# cm4_adc.net
KiCad netlist of a schematic drawn in EAGLE
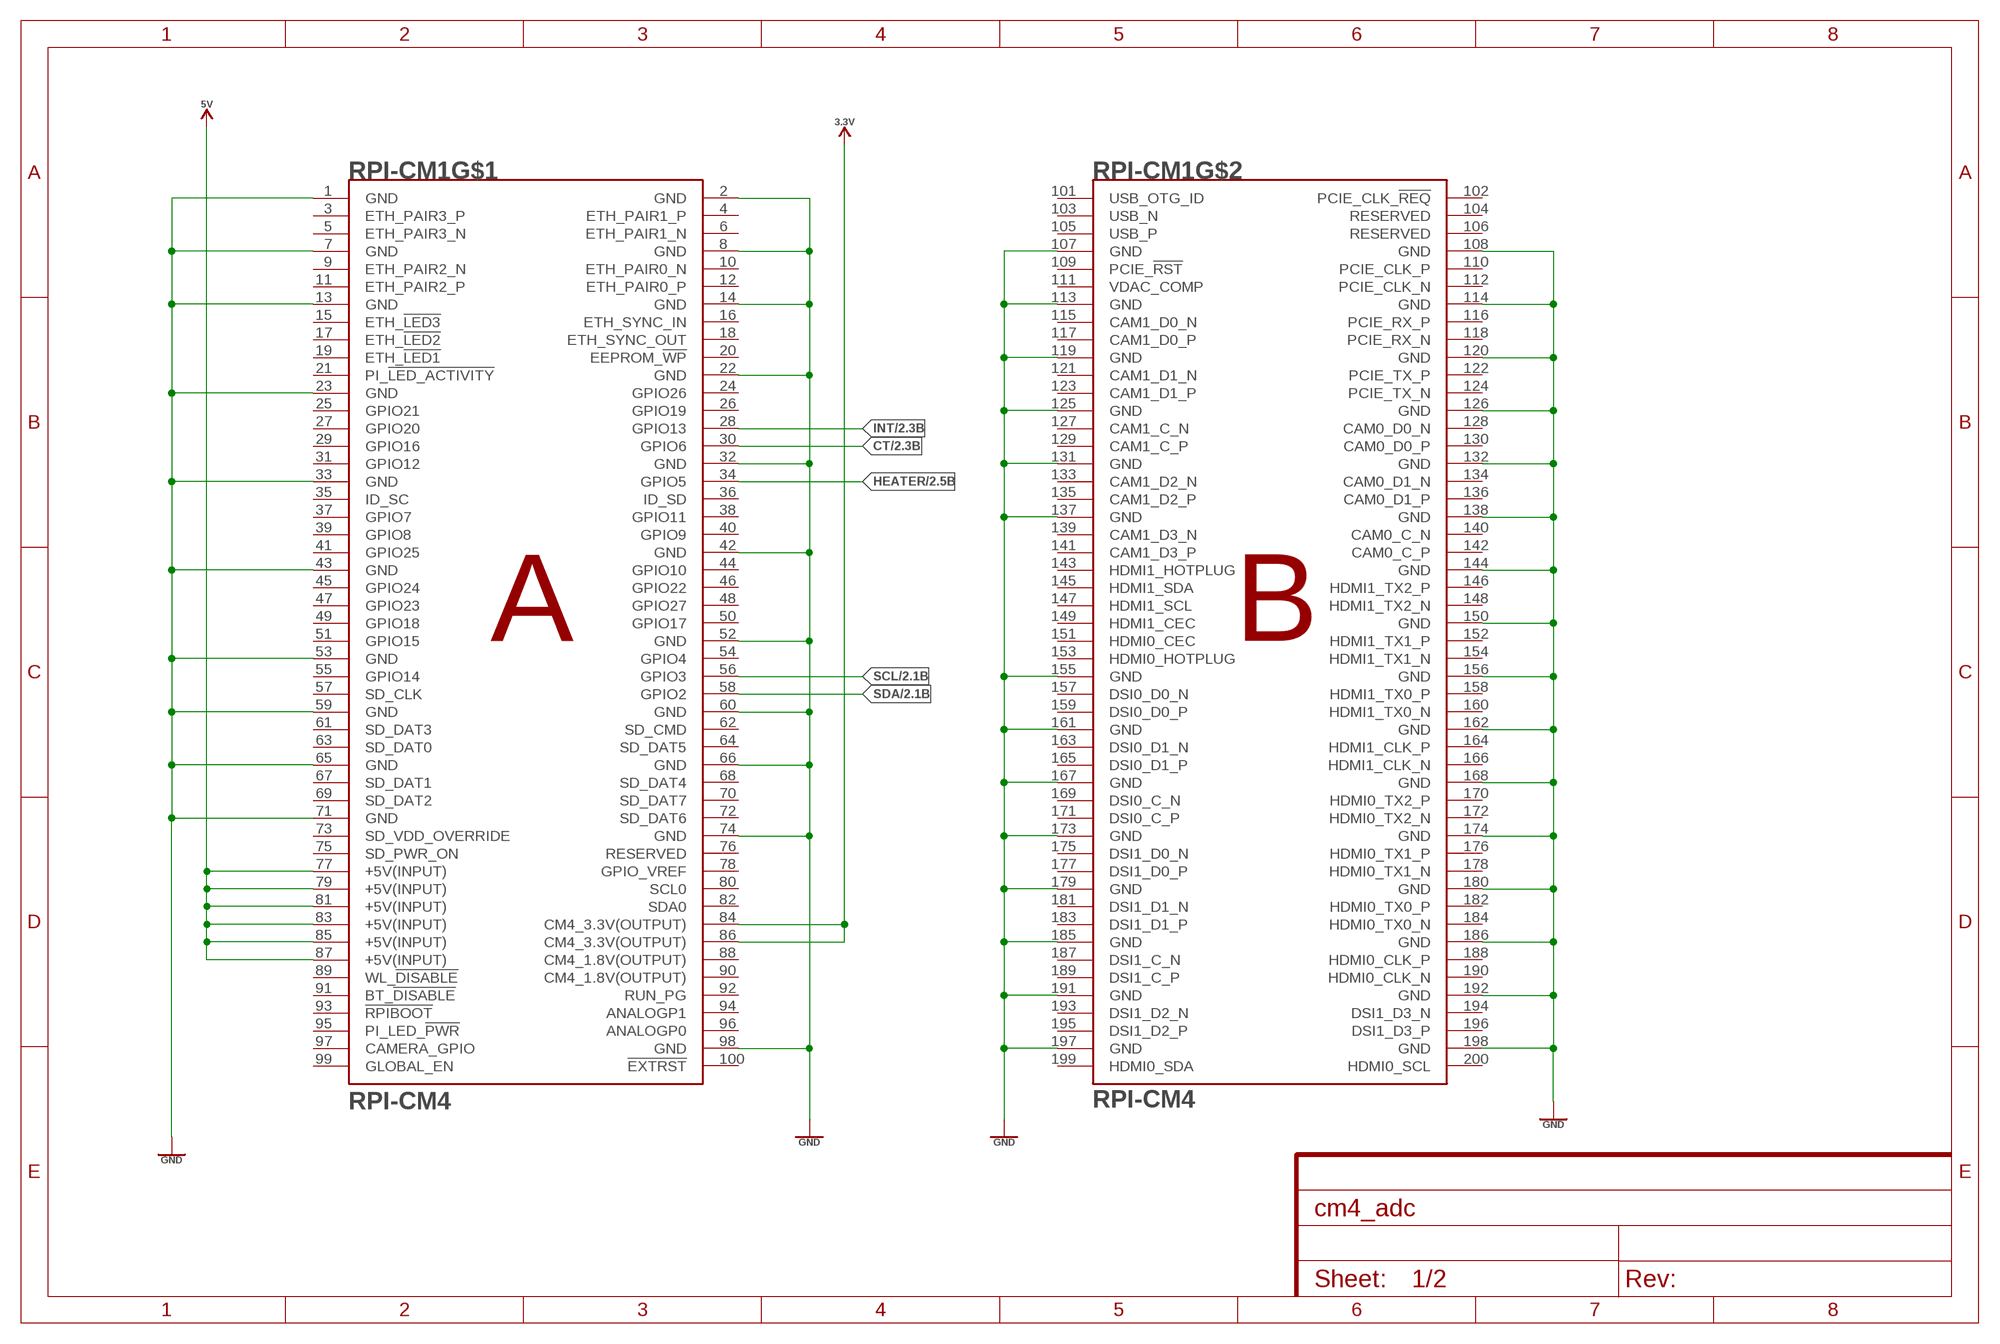
[diagram p0: schematic, sheet 1]
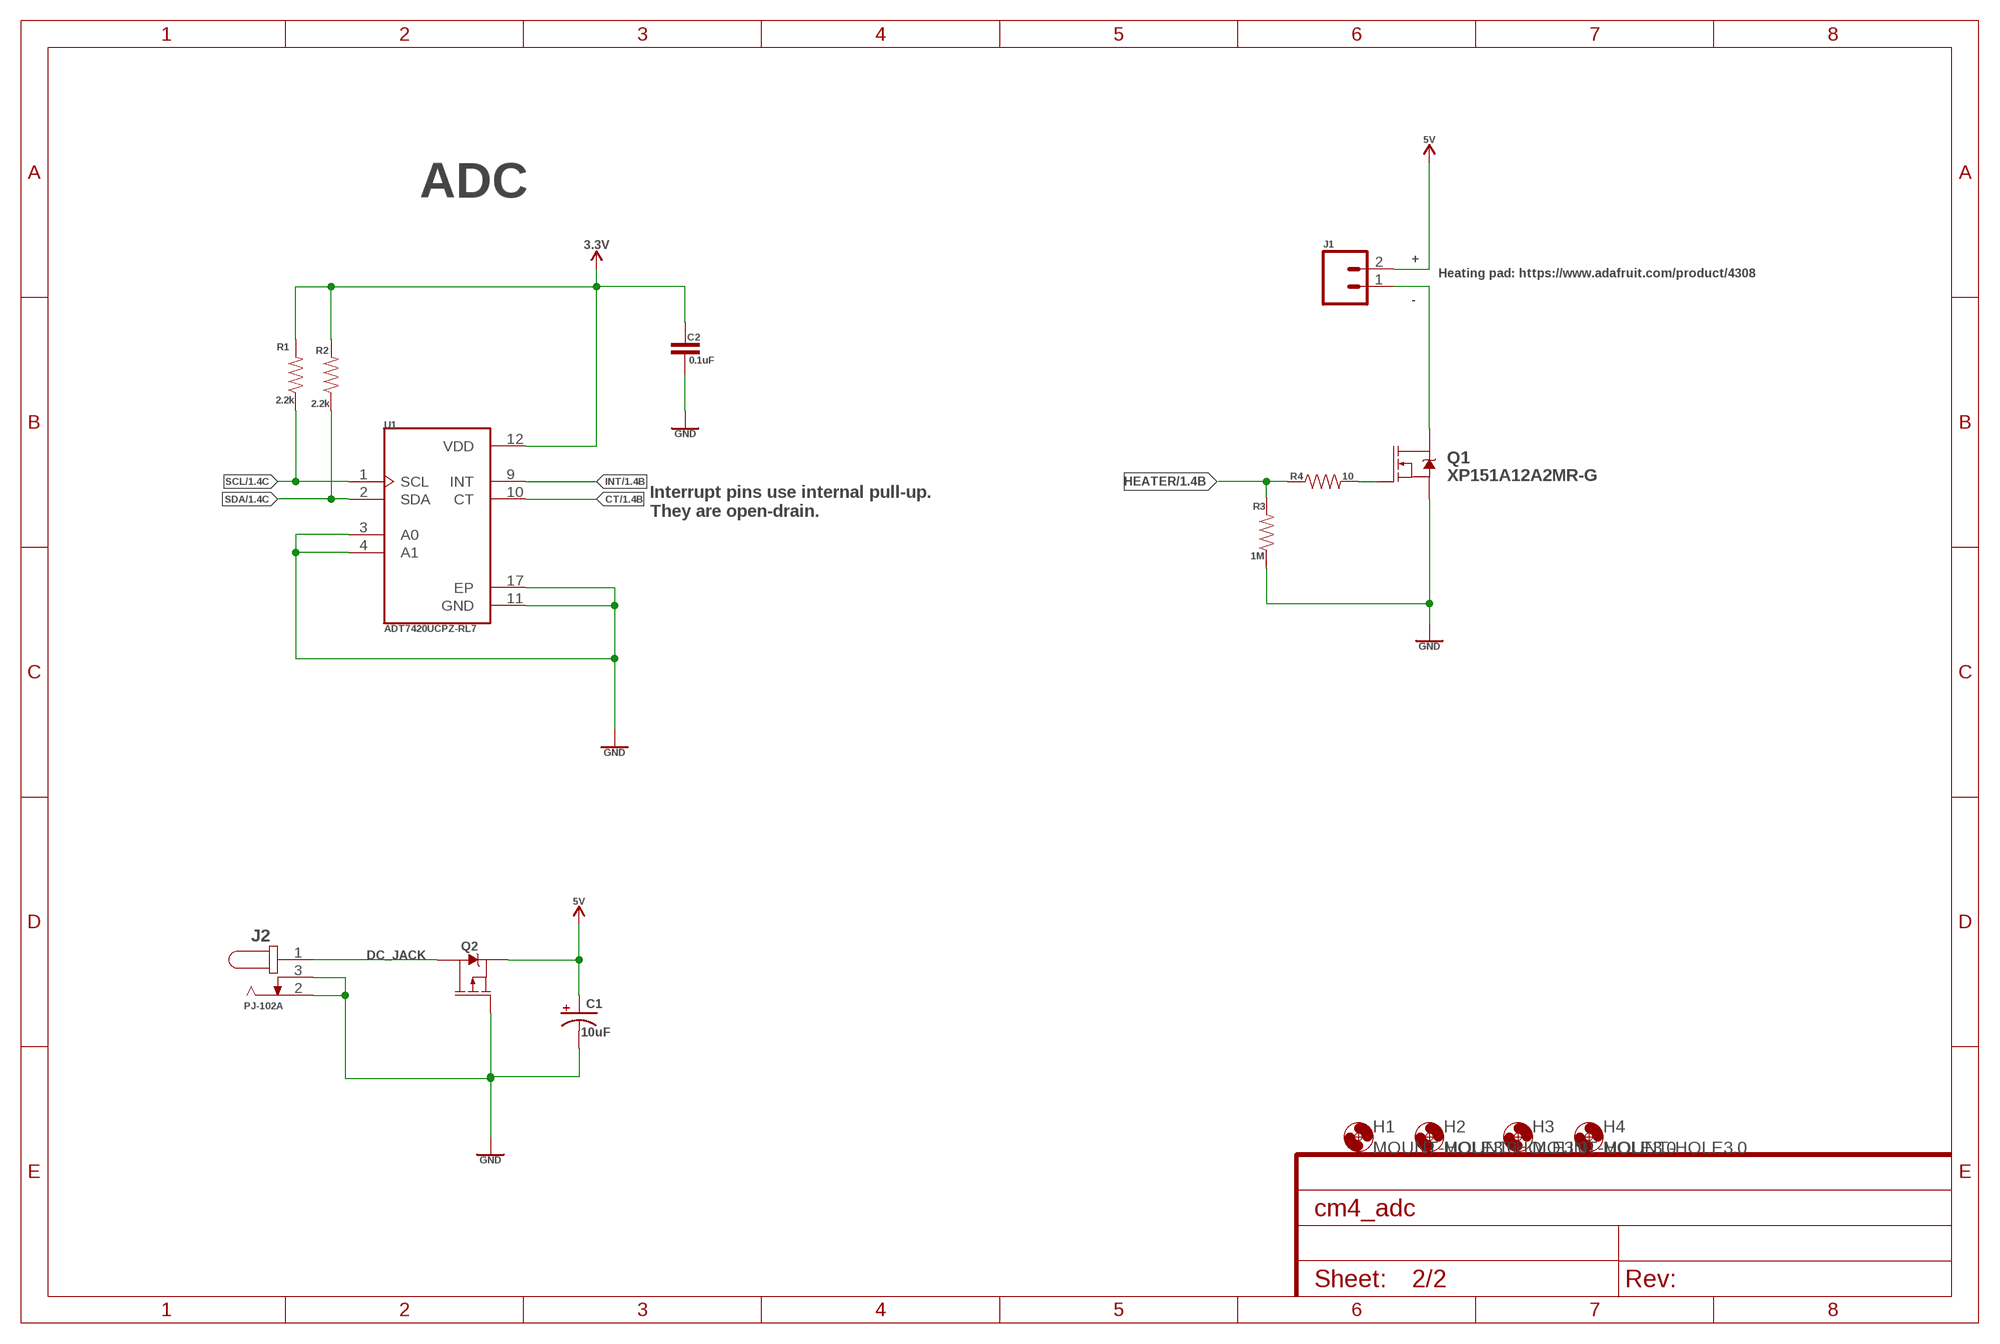
[diagram p1: schematic, sheet 2]

(export (version "E")
  (design (tool "Eeschema 10.0.6"))
  (components
    (comp (ref "RPI-CM1")
      (value "RPI-CM4")
      (footprint "eagle-import:RPI-CM4")
      (libsource (lib "eagle-import") (part "RPI-CM4"))
    )
    (comp (ref "C1")
      (value "10uF")
      (footprint "eagle-import:EIA3216")
      (libsource (lib "eagle-import") (part "10UF-POLAR-EIA3216-16V-10%(TANT)"))
    )
    (comp (ref "C2")
      (value "0.1uF")
      (footprint "eagle-import:0603")
      (libsource (lib "eagle-import") (part "0.1UF-0603-25V-(+80/-20%)"))
    )
    (comp (ref "H1")
      (value "MOUNT-HOLE3.0")
      (footprint "eagle-import:3,0")
      (libsource (lib "eagle-import") (part "MOUNT-HOLE3.0"))
    )
    (comp (ref "H2")
      (value "MOUNT-HOLE3.0")
      (footprint "eagle-import:3,0")
      (libsource (lib "eagle-import") (part "MOUNT-HOLE3.0"))
    )
    (comp (ref "H3")
      (value "MOUNT-HOLE3.0")
      (footprint "eagle-import:3,0")
      (libsource (lib "eagle-import") (part "MOUNT-HOLE3.0"))
    )
    (comp (ref "H4")
      (value "MOUNT-HOLE3.0")
      (footprint "eagle-import:3,0")
      (libsource (lib "eagle-import") (part "MOUNT-HOLE3.0"))
    )
    (comp (ref "J1")
      (value "CONN_023.5MM")
      (footprint "eagle-import:SCREWTERMINAL-3.5MM-2")
      (libsource (lib "eagle-import") (part "CONN_023.5MM"))
    )
    (comp (ref "J2")
      (value "PJ-102A")
      (footprint "eagle-import:CUI_PJ-102A")
      (fields (field (name "MANUFACTURER") "CUI INC"))
      (libsource (lib "eagle-import") (part "PJ-102A"))
    )
    (comp (ref "Q1")
      (value "XP151A12A2MR-G")
      (footprint "eagle-import:SOT323")
      (libsource (lib "eagle-import") (part "MOSFET-NCH-2N7002PW"))
    )
    (comp (ref "Q2")
      (value "2.5A/30V/105mΩ")
      (footprint "eagle-import:SOT23-3")
      (libsource (lib "eagle-import") (part "MOSFET_PCH-DMG2307L"))
    )
    (comp (ref "R1")
      (value "2.2k")
      (footprint "eagle-import:0603")
      (libsource (lib "eagle-import") (part "2.2KOHM-0603-1/10W-1%"))
    )
    (comp (ref "R2")
      (value "2.2k")
      (footprint "eagle-import:0603")
      (libsource (lib "eagle-import") (part "2.2KOHM-0603-1/10W-1%"))
    )
    (comp (ref "R3")
      (value "1M")
      (footprint "eagle-import:0603")
      (libsource (lib "eagle-import") (part "1MOHM-0603-1/4W-5%"))
    )
    (comp (ref "R4")
      (value "10")
      (footprint "eagle-import:0603")
      (libsource (lib "eagle-import") (part "10OHM-0603-1/10W-1%"))
    )
    (comp (ref "U1")
      (value "ADT7420UCPZ-RL7")
      (footprint "eagle-import:QFN65P400X400X80-17N")
      (fields (field (name "MF") "Analog Devices"))
      (libsource (lib "eagle-import") (part "ADT7420UCPZ-RL7"))
    )
  )
  (nets
    (net (code "1") (name "3.3V") (class "Default")
      (node (ref "C2") (pin "1") (pinfunction "1_1") (pintype "passive"))
      (node (ref "R1") (pin "2") (pinfunction "2_2") (pintype "passive"))
      (node (ref "R2") (pin "2") (pinfunction "2_2") (pintype "passive"))
      (node (ref "RPI-CM1") (pin "84") (pinfunction "CM4_3.3V(OUTPUT)_84") (pintype "passive"))
      (node (ref "RPI-CM1") (pin "86") (pinfunction "CM4_3.3V(OUTPUT)_86") (pintype "passive"))
      (node (ref "U1") (pin "12") (pinfunction "VDD_12") (pintype "power_in"))
    )
    (net (code "2") (name "5V") (class "Default")
      (node (ref "C1") (pin "+") (pinfunction "+_+") (pintype "passive"))
      (node (ref "J1") (pin "2") (pinfunction "2_2") (pintype "passive"))
      (node (ref "Q2") (pin "2") (pinfunction "S_2") (pintype "bidirectional"))
      (node (ref "RPI-CM1") (pin "77") (pinfunction "+5V(INPUT)_77") (pintype "passive"))
      (node (ref "RPI-CM1") (pin "79") (pinfunction "+5V(INPUT)_79") (pintype "passive"))
      (node (ref "RPI-CM1") (pin "81") (pinfunction "+5V(INPUT)_81") (pintype "passive"))
      (node (ref "RPI-CM1") (pin "83") (pinfunction "+5V(INPUT)_83") (pintype "passive"))
      (node (ref "RPI-CM1") (pin "85") (pinfunction "+5V(INPUT)_85") (pintype "passive"))
      (node (ref "RPI-CM1") (pin "87") (pinfunction "+5V(INPUT)_87") (pintype "passive"))
    )
    (net (code "3") (name "CT") (class "Default")
      (node (ref "RPI-CM1") (pin "30") (pinfunction "GPIO6_30") (pintype "passive"))
      (node (ref "U1") (pin "10") (pinfunction "CT_10") (pintype "output"))
    )
    (net (code "4") (name "DC_JACK") (class "Default")
      (node (ref "J2") (pin "1") (pinfunction "1_1") (pintype "passive"))
      (node (ref "Q2") (pin "3") (pinfunction "D_3") (pintype "bidirectional"))
    )
    (net (code "5") (name "GND") (class "Default")
      (node (ref "C1") (pin "-") (pinfunction "-_-") (pintype "passive"))
      (node (ref "C2") (pin "2") (pinfunction "2_2") (pintype "passive"))
      (node (ref "J2") (pin "2") (pinfunction "2_2") (pintype "passive"))
      (node (ref "J2") (pin "3") (pinfunction "3_3") (pintype "passive"))
      (node (ref "Q1") (pin "2") (pinfunction "S_2") (pintype "bidirectional"))
      (node (ref "Q2") (pin "1") (pinfunction "G_1") (pintype "bidirectional"))
      (node (ref "R3") (pin "1") (pinfunction "1_1") (pintype "passive"))
      (node (ref "RPI-CM1") (pin "1") (pinfunction "GND_1") (pintype "passive"))
      (node (ref "RPI-CM1") (pin "107") (pinfunction "GND_107") (pintype "passive"))
      (node (ref "RPI-CM1") (pin "108") (pinfunction "GND_108") (pintype "passive"))
      (node (ref "RPI-CM1") (pin "113") (pinfunction "GND_113") (pintype "passive"))
      (node (ref "RPI-CM1") (pin "114") (pinfunction "GND_114") (pintype "passive"))
      (node (ref "RPI-CM1") (pin "119") (pinfunction "GND_119") (pintype "passive"))
      (node (ref "RPI-CM1") (pin "120") (pinfunction "GND_120") (pintype "passive"))
      (node (ref "RPI-CM1") (pin "125") (pinfunction "GND_125") (pintype "passive"))
      (node (ref "RPI-CM1") (pin "126") (pinfunction "GND_126") (pintype "passive"))
      (node (ref "RPI-CM1") (pin "13") (pinfunction "GND_13") (pintype "passive"))
      (node (ref "RPI-CM1") (pin "131") (pinfunction "GND_131") (pintype "passive"))
      (node (ref "RPI-CM1") (pin "132") (pinfunction "GND_132") (pintype "passive"))
      (node (ref "RPI-CM1") (pin "137") (pinfunction "GND_137") (pintype "passive"))
      (node (ref "RPI-CM1") (pin "138") (pinfunction "GND_138") (pintype "passive"))
      (node (ref "RPI-CM1") (pin "14") (pinfunction "GND_14") (pintype "passive"))
      (node (ref "RPI-CM1") (pin "144") (pinfunction "GND_144") (pintype "passive"))
      (node (ref "RPI-CM1") (pin "150") (pinfunction "GND_150") (pintype "passive"))
      (node (ref "RPI-CM1") (pin "155") (pinfunction "GND_155") (pintype "passive"))
      (node (ref "RPI-CM1") (pin "156") (pinfunction "GND_156") (pintype "passive"))
      (node (ref "RPI-CM1") (pin "161") (pinfunction "GND_161") (pintype "passive"))
      (node (ref "RPI-CM1") (pin "162") (pinfunction "GND_162") (pintype "passive"))
      (node (ref "RPI-CM1") (pin "167") (pinfunction "GND_167") (pintype "passive"))
      (node (ref "RPI-CM1") (pin "168") (pinfunction "GND_168") (pintype "passive"))
      (node (ref "RPI-CM1") (pin "173") (pinfunction "GND_173") (pintype "passive"))
      (node (ref "RPI-CM1") (pin "174") (pinfunction "GND_174") (pintype "passive"))
      (node (ref "RPI-CM1") (pin "179") (pinfunction "GND_179") (pintype "passive"))
      (node (ref "RPI-CM1") (pin "180") (pinfunction "GND_180") (pintype "passive"))
      (node (ref "RPI-CM1") (pin "185") (pinfunction "GND_185") (pintype "passive"))
      (node (ref "RPI-CM1") (pin "186") (pinfunction "GND_186") (pintype "passive"))
      (node (ref "RPI-CM1") (pin "191") (pinfunction "GND_191") (pintype "passive"))
      (node (ref "RPI-CM1") (pin "192") (pinfunction "GND_192") (pintype "passive"))
      (node (ref "RPI-CM1") (pin "197") (pinfunction "GND_197") (pintype "passive"))
      (node (ref "RPI-CM1") (pin "198") (pinfunction "GND_198") (pintype "passive"))
      (node (ref "RPI-CM1") (pin "2") (pinfunction "GND_2") (pintype "passive"))
      (node (ref "RPI-CM1") (pin "22") (pinfunction "GND_22") (pintype "passive"))
      (node (ref "RPI-CM1") (pin "23") (pinfunction "GND_23") (pintype "passive"))
      (node (ref "RPI-CM1") (pin "32") (pinfunction "GND_32") (pintype "passive"))
      (node (ref "RPI-CM1") (pin "33") (pinfunction "GND_33") (pintype "passive"))
      (node (ref "RPI-CM1") (pin "42") (pinfunction "GND_42") (pintype "passive"))
      (node (ref "RPI-CM1") (pin "43") (pinfunction "GND_43") (pintype "passive"))
      (node (ref "RPI-CM1") (pin "52") (pinfunction "GND_52") (pintype "passive"))
      (node (ref "RPI-CM1") (pin "53") (pinfunction "GND_53") (pintype "passive"))
      (node (ref "RPI-CM1") (pin "59") (pinfunction "GND_59") (pintype "passive"))
      (node (ref "RPI-CM1") (pin "60") (pinfunction "GND_60") (pintype "passive"))
      (node (ref "RPI-CM1") (pin "65") (pinfunction "GND_65") (pintype "passive"))
      (node (ref "RPI-CM1") (pin "66") (pinfunction "GND_66") (pintype "passive"))
      (node (ref "RPI-CM1") (pin "7") (pinfunction "GND_7") (pintype "passive"))
      (node (ref "RPI-CM1") (pin "71") (pinfunction "GND_71") (pintype "passive"))
      (node (ref "RPI-CM1") (pin "74") (pinfunction "GND_74") (pintype "passive"))
      (node (ref "RPI-CM1") (pin "8") (pinfunction "GND_8") (pintype "passive"))
      (node (ref "RPI-CM1") (pin "98") (pinfunction "GND_98") (pintype "passive"))
      (node (ref "U1") (pin "11") (pinfunction "GND_11") (pintype "power_in"))
      (node (ref "U1") (pin "17") (pinfunction "EP_17") (pintype "power_in"))
      (node (ref "U1") (pin "3") (pinfunction "A0_3") (pintype "input"))
      (node (ref "U1") (pin "4") (pinfunction "A1_4") (pintype "input"))
    )
    (net (code "6") (name "HEATER") (class "Default")
      (node (ref "R3") (pin "2") (pinfunction "2_2") (pintype "passive"))
      (node (ref "R4") (pin "1") (pinfunction "1_1") (pintype "passive"))
      (node (ref "RPI-CM1") (pin "34") (pinfunction "GPIO5_34") (pintype "passive"))
    )
    (net (code "7") (name "INT") (class "Default")
      (node (ref "RPI-CM1") (pin "28") (pinfunction "GPIO13_28") (pintype "passive"))
      (node (ref "U1") (pin "9") (pinfunction "INT_9") (pintype "output"))
    )
    (net (code "8") (name "Net-(Q1-D)") (class "Default")
      (node (ref "J1") (pin "1") (pinfunction "1_1") (pintype "passive"))
      (node (ref "Q1") (pin "3") (pinfunction "D_3") (pintype "bidirectional"))
    )
    (net (code "9") (name "Net-(Q1-G)") (class "Default")
      (node (ref "Q1") (pin "1") (pinfunction "G_1") (pintype "bidirectional"))
      (node (ref "R4") (pin "2") (pinfunction "2_2") (pintype "passive"))
    )
    (net (code "10") (name "SCL") (class "Default")
      (node (ref "R1") (pin "1") (pinfunction "1_1") (pintype "passive"))
      (node (ref "RPI-CM1") (pin "56") (pinfunction "GPIO3_56") (pintype "passive"))
      (node (ref "U1") (pin "1") (pinfunction "SCL_1") (pintype "input"))
    )
    (net (code "11") (name "SDA") (class "Default")
      (node (ref "R2") (pin "1") (pinfunction "1_1") (pintype "passive"))
      (node (ref "RPI-CM1") (pin "58") (pinfunction "GPIO2_58") (pintype "passive"))
      (node (ref "U1") (pin "2") (pinfunction "SDA_2") (pintype "bidirectional"))
    )
    (net (code "12") (name "unconnected-(RPI-CM1A-ANALOGP0-Pad96)") (class "Default")
      (node (ref "RPI-CM1") (pin "96") (pinfunction "ANALOGP0_96") (pintype "passive"))
    )
    (net (code "13") (name "unconnected-(RPI-CM1A-ANALOGP1-Pad94)") (class "Default")
      (node (ref "RPI-CM1") (pin "94") (pinfunction "ANALOGP1_94") (pintype "passive"))
    )
    (net (code "14") (name "unconnected-(RPI-CM1A-BT_~{DISABLE}-Pad91)") (class "Default")
      (node (ref "RPI-CM1") (pin "91") (pinfunction "BT_~{DISABLE}_91") (pintype "passive"))
    )
    (net (code "15") (name "unconnected-(RPI-CM1A-CAMERA_GPIO-Pad97)") (class "Default")
      (node (ref "RPI-CM1") (pin "97") (pinfunction "CAMERA_GPIO_97") (pintype "passive"))
    )
    (net (code "16") (name "unconnected-(RPI-CM1A-CM4_1.8V(OUTPUT)-Pad88)") (class "Default")
      (node (ref "RPI-CM1") (pin "88") (pinfunction "CM4_1.8V(OUTPUT)_88") (pintype "passive"))
    )
    (net (code "17") (name "unconnected-(RPI-CM1A-CM4_1.8V(OUTPUT)-Pad90)") (class "Default")
      (node (ref "RPI-CM1") (pin "90") (pinfunction "CM4_1.8V(OUTPUT)_90") (pintype "passive"))
    )
    (net (code "18") (name "unconnected-(RPI-CM1A-EEPROM_~{WP}-Pad20)") (class "Default")
      (node (ref "RPI-CM1") (pin "20") (pinfunction "EEPROM_~{WP}_20") (pintype "passive"))
    )
    (net (code "19") (name "unconnected-(RPI-CM1A-ETH_PAIR0_N-Pad10)") (class "Default")
      (node (ref "RPI-CM1") (pin "10") (pinfunction "ETH_PAIR0_N_10") (pintype "passive"))
    )
    (net (code "20") (name "unconnected-(RPI-CM1A-ETH_PAIR0_P-Pad12)") (class "Default")
      (node (ref "RPI-CM1") (pin "12") (pinfunction "ETH_PAIR0_P_12") (pintype "passive"))
    )
    (net (code "21") (name "unconnected-(RPI-CM1A-ETH_PAIR1_N-Pad6)") (class "Default")
      (node (ref "RPI-CM1") (pin "6") (pinfunction "ETH_PAIR1_N_6") (pintype "passive"))
    )
    (net (code "22") (name "unconnected-(RPI-CM1A-ETH_PAIR1_P-Pad4)") (class "Default")
      (node (ref "RPI-CM1") (pin "4") (pinfunction "ETH_PAIR1_P_4") (pintype "passive"))
    )
    (net (code "23") (name "unconnected-(RPI-CM1A-ETH_PAIR2_N-Pad9)") (class "Default")
      (node (ref "RPI-CM1") (pin "9") (pinfunction "ETH_PAIR2_N_9") (pintype "passive"))
    )
    (net (code "24") (name "unconnected-(RPI-CM1A-ETH_PAIR2_P-Pad11)") (class "Default")
      (node (ref "RPI-CM1") (pin "11") (pinfunction "ETH_PAIR2_P_11") (pintype "passive"))
    )
    (net (code "25") (name "unconnected-(RPI-CM1A-ETH_PAIR3_N-Pad5)") (class "Default")
      (node (ref "RPI-CM1") (pin "5") (pinfunction "ETH_PAIR3_N_5") (pintype "passive"))
    )
    (net (code "26") (name "unconnected-(RPI-CM1A-ETH_PAIR3_P-Pad3)") (class "Default")
      (node (ref "RPI-CM1") (pin "3") (pinfunction "ETH_PAIR3_P_3") (pintype "passive"))
    )
    (net (code "27") (name "unconnected-(RPI-CM1A-ETH_SYNC_IN-Pad16)") (class "Default")
      (node (ref "RPI-CM1") (pin "16") (pinfunction "ETH_SYNC_IN_16") (pintype "passive"))
    )
    (net (code "28") (name "unconnected-(RPI-CM1A-ETH_SYNC_OUT-Pad18)") (class "Default")
      (node (ref "RPI-CM1") (pin "18") (pinfunction "ETH_SYNC_OUT_18") (pintype "passive"))
    )
    (net (code "29") (name "unconnected-(RPI-CM1A-ETH_~{LED1}-Pad19)") (class "Default")
      (node (ref "RPI-CM1") (pin "19") (pinfunction "ETH_~{LED1}_19") (pintype "passive"))
    )
    (net (code "30") (name "unconnected-(RPI-CM1A-ETH_~{LED2}-Pad17)") (class "Default")
      (node (ref "RPI-CM1") (pin "17") (pinfunction "ETH_~{LED2}_17") (pintype "passive"))
    )
    (net (code "31") (name "unconnected-(RPI-CM1A-ETH_~{LED3}-Pad15)") (class "Default")
      (node (ref "RPI-CM1") (pin "15") (pinfunction "ETH_~{LED3}_15") (pintype "passive"))
    )
    (net (code "32") (name "unconnected-(RPI-CM1A-GLOBAL_EN-Pad99)") (class "Default")
      (node (ref "RPI-CM1") (pin "99") (pinfunction "GLOBAL_EN_99") (pintype "passive"))
    )
    (net (code "33") (name "unconnected-(RPI-CM1A-GPIO4-Pad54)") (class "Default")
      (node (ref "RPI-CM1") (pin "54") (pinfunction "GPIO4_54") (pintype "passive"))
    )
    (net (code "34") (name "unconnected-(RPI-CM1A-GPIO7-Pad37)") (class "Default")
      (node (ref "RPI-CM1") (pin "37") (pinfunction "GPIO7_37") (pintype "passive"))
    )
    (net (code "35") (name "unconnected-(RPI-CM1A-GPIO8-Pad39)") (class "Default")
      (node (ref "RPI-CM1") (pin "39") (pinfunction "GPIO8_39") (pintype "passive"))
    )
    (net (code "36") (name "unconnected-(RPI-CM1A-GPIO9-Pad40)") (class "Default")
      (node (ref "RPI-CM1") (pin "40") (pinfunction "GPIO9_40") (pintype "passive"))
    )
    (net (code "37") (name "unconnected-(RPI-CM1A-GPIO10-Pad44)") (class "Default")
      (node (ref "RPI-CM1") (pin "44") (pinfunction "GPIO10_44") (pintype "passive"))
    )
    (net (code "38") (name "unconnected-(RPI-CM1A-GPIO11-Pad38)") (class "Default")
      (node (ref "RPI-CM1") (pin "38") (pinfunction "GPIO11_38") (pintype "passive"))
    )
    (net (code "39") (name "unconnected-(RPI-CM1A-GPIO12-Pad31)") (class "Default")
      (node (ref "RPI-CM1") (pin "31") (pinfunction "GPIO12_31") (pintype "passive"))
    )
    (net (code "40") (name "unconnected-(RPI-CM1A-GPIO14-Pad55)") (class "Default")
      (node (ref "RPI-CM1") (pin "55") (pinfunction "GPIO14_55") (pintype "passive"))
    )
    (net (code "41") (name "unconnected-(RPI-CM1A-GPIO15-Pad51)") (class "Default")
      (node (ref "RPI-CM1") (pin "51") (pinfunction "GPIO15_51") (pintype "passive"))
    )
    (net (code "42") (name "unconnected-(RPI-CM1A-GPIO16-Pad29)") (class "Default")
      (node (ref "RPI-CM1") (pin "29") (pinfunction "GPIO16_29") (pintype "passive"))
    )
    (net (code "43") (name "unconnected-(RPI-CM1A-GPIO17-Pad50)") (class "Default")
      (node (ref "RPI-CM1") (pin "50") (pinfunction "GPIO17_50") (pintype "passive"))
    )
    (net (code "44") (name "unconnected-(RPI-CM1A-GPIO18-Pad49)") (class "Default")
      (node (ref "RPI-CM1") (pin "49") (pinfunction "GPIO18_49") (pintype "passive"))
    )
    (net (code "45") (name "unconnected-(RPI-CM1A-GPIO19-Pad26)") (class "Default")
      (node (ref "RPI-CM1") (pin "26") (pinfunction "GPIO19_26") (pintype "passive"))
    )
    (net (code "46") (name "unconnected-(RPI-CM1A-GPIO20-Pad27)") (class "Default")
      (node (ref "RPI-CM1") (pin "27") (pinfunction "GPIO20_27") (pintype "passive"))
    )
    (net (code "47") (name "unconnected-(RPI-CM1A-GPIO21-Pad25)") (class "Default")
      (node (ref "RPI-CM1") (pin "25") (pinfunction "GPIO21_25") (pintype "passive"))
    )
    (net (code "48") (name "unconnected-(RPI-CM1A-GPIO22-Pad46)") (class "Default")
      (node (ref "RPI-CM1") (pin "46") (pinfunction "GPIO22_46") (pintype "passive"))
    )
    (net (code "49") (name "unconnected-(RPI-CM1A-GPIO23-Pad47)") (class "Default")
      (node (ref "RPI-CM1") (pin "47") (pinfunction "GPIO23_47") (pintype "passive"))
    )
    (net (code "50") (name "unconnected-(RPI-CM1A-GPIO24-Pad45)") (class "Default")
      (node (ref "RPI-CM1") (pin "45") (pinfunction "GPIO24_45") (pintype "passive"))
    )
    (net (code "51") (name "unconnected-(RPI-CM1A-GPIO25-Pad41)") (class "Default")
      (node (ref "RPI-CM1") (pin "41") (pinfunction "GPIO25_41") (pintype "passive"))
    )
    (net (code "52") (name "unconnected-(RPI-CM1A-GPIO26-Pad24)") (class "Default")
      (node (ref "RPI-CM1") (pin "24") (pinfunction "GPIO26_24") (pintype "passive"))
    )
    (net (code "53") (name "unconnected-(RPI-CM1A-GPIO27-Pad48)") (class "Default")
      (node (ref "RPI-CM1") (pin "48") (pinfunction "GPIO27_48") (pintype "passive"))
    )
    (net (code "54") (name "unconnected-(RPI-CM1A-GPIO_VREF-Pad78)") (class "Default")
      (node (ref "RPI-CM1") (pin "78") (pinfunction "GPIO_VREF_78") (pintype "passive"))
    )
    (net (code "55") (name "unconnected-(RPI-CM1A-ID_SC-Pad35)") (class "Default")
      (node (ref "RPI-CM1") (pin "35") (pinfunction "ID_SC_35") (pintype "passive"))
    )
    (net (code "56") (name "unconnected-(RPI-CM1A-ID_SD-Pad36)") (class "Default")
      (node (ref "RPI-CM1") (pin "36") (pinfunction "ID_SD_36") (pintype "passive"))
    )
    (net (code "57") (name "unconnected-(RPI-CM1A-PI_LED_~{PWR}-Pad95)") (class "Default")
      (node (ref "RPI-CM1") (pin "95") (pinfunction "PI_LED_~{PWR}_95") (pintype "passive"))
    )
    (net (code "58") (name "unconnected-(RPI-CM1A-PI_~{LED_ACTIVITY}-Pad21)") (class "Default")
      (node (ref "RPI-CM1") (pin "21") (pinfunction "PI_~{LED_ACTIVITY}_21") (pintype "passive"))
    )
    (net (code "59") (name "unconnected-(RPI-CM1A-RESERVED-Pad76)") (class "Default")
      (node (ref "RPI-CM1") (pin "76") (pinfunction "RESERVED_76") (pintype "passive"))
    )
    (net (code "60") (name "unconnected-(RPI-CM1A-RUN_PG-Pad92)") (class "Default")
      (node (ref "RPI-CM1") (pin "92") (pinfunction "RUN_PG_92") (pintype "passive"))
    )
    (net (code "61") (name "unconnected-(RPI-CM1A-SCL0-Pad80)") (class "Default")
      (node (ref "RPI-CM1") (pin "80") (pinfunction "SCL0_80") (pintype "passive"))
    )
    (net (code "62") (name "unconnected-(RPI-CM1A-SDA0-Pad82)") (class "Default")
      (node (ref "RPI-CM1") (pin "82") (pinfunction "SDA0_82") (pintype "passive"))
    )
    (net (code "63") (name "unconnected-(RPI-CM1A-SD_CLK-Pad57)") (class "Default")
      (node (ref "RPI-CM1") (pin "57") (pinfunction "SD_CLK_57") (pintype "passive"))
    )
    (net (code "64") (name "unconnected-(RPI-CM1A-SD_CMD-Pad62)") (class "Default")
      (node (ref "RPI-CM1") (pin "62") (pinfunction "SD_CMD_62") (pintype "passive"))
    )
    (net (code "65") (name "unconnected-(RPI-CM1A-SD_DAT0-Pad63)") (class "Default")
      (node (ref "RPI-CM1") (pin "63") (pinfunction "SD_DAT0_63") (pintype "passive"))
    )
    (net (code "66") (name "unconnected-(RPI-CM1A-SD_DAT1-Pad67)") (class "Default")
      (node (ref "RPI-CM1") (pin "67") (pinfunction "SD_DAT1_67") (pintype "passive"))
    )
    (net (code "67") (name "unconnected-(RPI-CM1A-SD_DAT2-Pad69)") (class "Default")
      (node (ref "RPI-CM1") (pin "69") (pinfunction "SD_DAT2_69") (pintype "passive"))
    )
    (net (code "68") (name "unconnected-(RPI-CM1A-SD_DAT3-Pad61)") (class "Default")
      (node (ref "RPI-CM1") (pin "61") (pinfunction "SD_DAT3_61") (pintype "passive"))
    )
    (net (code "69") (name "unconnected-(RPI-CM1A-SD_DAT4-Pad68)") (class "Default")
      (node (ref "RPI-CM1") (pin "68") (pinfunction "SD_DAT4_68") (pintype "passive"))
    )
    (net (code "70") (name "unconnected-(RPI-CM1A-SD_DAT5-Pad64)") (class "Default")
      (node (ref "RPI-CM1") (pin "64") (pinfunction "SD_DAT5_64") (pintype "passive"))
    )
    (net (code "71") (name "unconnected-(RPI-CM1A-SD_DAT6-Pad72)") (class "Default")
      (node (ref "RPI-CM1") (pin "72") (pinfunction "SD_DAT6_72") (pintype "passive"))
    )
    (net (code "72") (name "unconnected-(RPI-CM1A-SD_DAT7-Pad70)") (class "Default")
      (node (ref "RPI-CM1") (pin "70") (pinfunction "SD_DAT7_70") (pintype "passive"))
    )
    (net (code "73") (name "unconnected-(RPI-CM1A-SD_PWR_ON-Pad75)") (class "Default")
      (node (ref "RPI-CM1") (pin "75") (pinfunction "SD_PWR_ON_75") (pintype "passive"))
    )
    (net (code "74") (name "unconnected-(RPI-CM1A-SD_VDD_OVERRIDE-Pad73)") (class "Default")
      (node (ref "RPI-CM1") (pin "73") (pinfunction "SD_VDD_OVERRIDE_73") (pintype "passive"))
    )
    (net (code "75") (name "unconnected-(RPI-CM1A-WL_~{DISABLE}-Pad89)") (class "Default")
      (node (ref "RPI-CM1") (pin "89") (pinfunction "WL_~{DISABLE}_89") (pintype "passive"))
    )
    (net (code "76") (name "unconnected-(RPI-CM1A-~{EXTRST}-Pad100)") (class "Default")
      (node (ref "RPI-CM1") (pin "100") (pinfunction "~{EXTRST}_100") (pintype "passive"))
    )
    (net (code "77") (name "unconnected-(RPI-CM1A-~{RPIBOOT}-Pad93)") (class "Default")
      (node (ref "RPI-CM1") (pin "93") (pinfunction "~{RPIBOOT}_93") (pintype "passive"))
    )
    (net (code "78") (name "unconnected-(RPI-CM1B-CAM0_C_N-Pad140)") (class "Default")
      (node (ref "RPI-CM1") (pin "140") (pinfunction "CAM0_C_N_140") (pintype "passive"))
    )
    (net (code "79") (name "unconnected-(RPI-CM1B-CAM0_C_P-Pad142)") (class "Default")
      (node (ref "RPI-CM1") (pin "142") (pinfunction "CAM0_C_P_142") (pintype "passive"))
    )
    (net (code "80") (name "unconnected-(RPI-CM1B-CAM0_D0_N-Pad128)") (class "Default")
      (node (ref "RPI-CM1") (pin "128") (pinfunction "CAM0_D0_N_128") (pintype "passive"))
    )
    (net (code "81") (name "unconnected-(RPI-CM1B-CAM0_D0_P-Pad130)") (class "Default")
      (node (ref "RPI-CM1") (pin "130") (pinfunction "CAM0_D0_P_130") (pintype "passive"))
    )
    (net (code "82") (name "unconnected-(RPI-CM1B-CAM0_D1_N-Pad134)") (class "Default")
      (node (ref "RPI-CM1") (pin "134") (pinfunction "CAM0_D1_N_134") (pintype "passive"))
    )
    (net (code "83") (name "unconnected-(RPI-CM1B-CAM0_D1_P-Pad136)") (class "Default")
      (node (ref "RPI-CM1") (pin "136") (pinfunction "CAM0_D1_P_136") (pintype "passive"))
    )
    (net (code "84") (name "unconnected-(RPI-CM1B-CAM1_C_N-Pad127)") (class "Default")
      (node (ref "RPI-CM1") (pin "127") (pinfunction "CAM1_C_N_127") (pintype "passive"))
    )
    (net (code "85") (name "unconnected-(RPI-CM1B-CAM1_C_P-Pad129)") (class "Default")
      (node (ref "RPI-CM1") (pin "129") (pinfunction "CAM1_C_P_129") (pintype "passive"))
    )
    (net (code "86") (name "unconnected-(RPI-CM1B-CAM1_D0_N-Pad115)") (class "Default")
      (node (ref "RPI-CM1") (pin "115") (pinfunction "CAM1_D0_N_115") (pintype "passive"))
    )
    (net (code "87") (name "unconnected-(RPI-CM1B-CAM1_D0_P-Pad117)") (class "Default")
      (node (ref "RPI-CM1") (pin "117") (pinfunction "CAM1_D0_P_117") (pintype "passive"))
    )
    (net (code "88") (name "unconnected-(RPI-CM1B-CAM1_D1_N-Pad121)") (class "Default")
      (node (ref "RPI-CM1") (pin "121") (pinfunction "CAM1_D1_N_121") (pintype "passive"))
    )
    (net (code "89") (name "unconnected-(RPI-CM1B-CAM1_D1_P-Pad123)") (class "Default")
      (node (ref "RPI-CM1") (pin "123") (pinfunction "CAM1_D1_P_123") (pintype "passive"))
    )
    (net (code "90") (name "unconnected-(RPI-CM1B-CAM1_D2_N-Pad133)") (class "Default")
      (node (ref "RPI-CM1") (pin "133") (pinfunction "CAM1_D2_N_133") (pintype "passive"))
    )
    (net (code "91") (name "unconnected-(RPI-CM1B-CAM1_D2_P-Pad135)") (class "Default")
      (node (ref "RPI-CM1") (pin "135") (pinfunction "CAM1_D2_P_135") (pintype "passive"))
    )
    (net (code "92") (name "unconnected-(RPI-CM1B-CAM1_D3_N-Pad139)") (class "Default")
      (node (ref "RPI-CM1") (pin "139") (pinfunction "CAM1_D3_N_139") (pintype "passive"))
    )
    (net (code "93") (name "unconnected-(RPI-CM1B-CAM1_D3_P-Pad141)") (class "Default")
      (node (ref "RPI-CM1") (pin "141") (pinfunction "CAM1_D3_P_141") (pintype "passive"))
    )
    (net (code "94") (name "unconnected-(RPI-CM1B-DSI0_C_N-Pad169)") (class "Default")
      (node (ref "RPI-CM1") (pin "169") (pinfunction "DSI0_C_N_169") (pintype "passive"))
    )
    (net (code "95") (name "unconnected-(RPI-CM1B-DSI0_C_P-Pad171)") (class "Default")
      (node (ref "RPI-CM1") (pin "171") (pinfunction "DSI0_C_P_171") (pintype "passive"))
    )
    (net (code "96") (name "unconnected-(RPI-CM1B-DSI0_D0_N-Pad157)") (class "Default")
      (node (ref "RPI-CM1") (pin "157") (pinfunction "DSI0_D0_N_157") (pintype "passive"))
    )
    (net (code "97") (name "unconnected-(RPI-CM1B-DSI0_D0_P-Pad159)") (class "Default")
      (node (ref "RPI-CM1") (pin "159") (pinfunction "DSI0_D0_P_159") (pintype "passive"))
    )
    (net (code "98") (name "unconnected-(RPI-CM1B-DSI0_D1_N-Pad163)") (class "Default")
      (node (ref "RPI-CM1") (pin "163") (pinfunction "DSI0_D1_N_163") (pintype "passive"))
    )
    (net (code "99") (name "unconnected-(RPI-CM1B-DSI0_D1_P-Pad165)") (class "Default")
      (node (ref "RPI-CM1") (pin "165") (pinfunction "DSI0_D1_P_165") (pintype "passive"))
    )
    (net (code "100") (name "unconnected-(RPI-CM1B-DSI1_C_N-Pad187)") (class "Default")
      (node (ref "RPI-CM1") (pin "187") (pinfunction "DSI1_C_N_187") (pintype "passive"))
    )
    (net (code "101") (name "unconnected-(RPI-CM1B-DSI1_C_P-Pad189)") (class "Default")
      (node (ref "RPI-CM1") (pin "189") (pinfunction "DSI1_C_P_189") (pintype "passive"))
    )
    (net (code "102") (name "unconnected-(RPI-CM1B-DSI1_D0_N-Pad175)") (class "Default")
      (node (ref "RPI-CM1") (pin "175") (pinfunction "DSI1_D0_N_175") (pintype "passive"))
    )
    (net (code "103") (name "unconnected-(RPI-CM1B-DSI1_D0_P-Pad177)") (class "Default")
      (node (ref "RPI-CM1") (pin "177") (pinfunction "DSI1_D0_P_177") (pintype "passive"))
    )
    (net (code "104") (name "unconnected-(RPI-CM1B-DSI1_D1_N-Pad181)") (class "Default")
      (node (ref "RPI-CM1") (pin "181") (pinfunction "DSI1_D1_N_181") (pintype "passive"))
    )
    (net (code "105") (name "unconnected-(RPI-CM1B-DSI1_D1_P-Pad183)") (class "Default")
      (node (ref "RPI-CM1") (pin "183") (pinfunction "DSI1_D1_P_183") (pintype "passive"))
    )
    (net (code "106") (name "unconnected-(RPI-CM1B-DSI1_D2_N-Pad193)") (class "Default")
      (node (ref "RPI-CM1") (pin "193") (pinfunction "DSI1_D2_N_193") (pintype "passive"))
    )
    (net (code "107") (name "unconnected-(RPI-CM1B-DSI1_D2_P-Pad195)") (class "Default")
      (node (ref "RPI-CM1") (pin "195") (pinfunction "DSI1_D2_P_195") (pintype "passive"))
    )
    (net (code "108") (name "unconnected-(RPI-CM1B-DSI1_D3_N-Pad194)") (class "Default")
      (node (ref "RPI-CM1") (pin "194") (pinfunction "DSI1_D3_N_194") (pintype "passive"))
    )
    (net (code "109") (name "unconnected-(RPI-CM1B-DSI1_D3_P-Pad196)") (class "Default")
      (node (ref "RPI-CM1") (pin "196") (pinfunction "DSI1_D3_P_196") (pintype "passive"))
    )
    (net (code "110") (name "unconnected-(RPI-CM1B-HDMI0_CEC-Pad151)") (class "Default")
      (node (ref "RPI-CM1") (pin "151") (pinfunction "HDMI0_CEC_151") (pintype "passive"))
    )
    (net (code "111") (name "unconnected-(RPI-CM1B-HDMI0_CLK_N-Pad190)") (class "Default")
      (node (ref "RPI-CM1") (pin "190") (pinfunction "HDMI0_CLK_N_190") (pintype "passive"))
    )
    (net (code "112") (name "unconnected-(RPI-CM1B-HDMI0_CLK_P-Pad188)") (class "Default")
      (node (ref "RPI-CM1") (pin "188") (pinfunction "HDMI0_CLK_P_188") (pintype "passive"))
    )
    (net (code "113") (name "unconnected-(RPI-CM1B-HDMI0_HOTPLUG-Pad153)") (class "Default")
      (node (ref "RPI-CM1") (pin "153") (pinfunction "HDMI0_HOTPLUG_153") (pintype "passive"))
    )
    (net (code "114") (name "unconnected-(RPI-CM1B-HDMI0_SCL-Pad200)") (class "Default")
      (node (ref "RPI-CM1") (pin "200") (pinfunction "HDMI0_SCL_200") (pintype "passive"))
    )
    (net (code "115") (name "unconnected-(RPI-CM1B-HDMI0_SDA-Pad199)") (class "Default")
      (node (ref "RPI-CM1") (pin "199") (pinfunction "HDMI0_SDA_199") (pintype "passive"))
    )
    (net (code "116") (name "unconnected-(RPI-CM1B-HDMI0_TX0_N-Pad184)") (class "Default")
      (node (ref "RPI-CM1") (pin "184") (pinfunction "HDMI0_TX0_N_184") (pintype "passive"))
    )
    (net (code "117") (name "unconnected-(RPI-CM1B-HDMI0_TX0_P-Pad182)") (class "Default")
      (node (ref "RPI-CM1") (pin "182") (pinfunction "HDMI0_TX0_P_182") (pintype "passive"))
    )
    (net (code "118") (name "unconnected-(RPI-CM1B-HDMI0_TX1_N-Pad178)") (class "Default")
      (node (ref "RPI-CM1") (pin "178") (pinfunction "HDMI0_TX1_N_178") (pintype "passive"))
    )
    (net (code "119") (name "unconnected-(RPI-CM1B-HDMI0_TX1_P-Pad176)") (class "Default")
      (node (ref "RPI-CM1") (pin "176") (pinfunction "HDMI0_TX1_P_176") (pintype "passive"))
    )
    (net (code "120") (name "unconnected-(RPI-CM1B-HDMI0_TX2_N-Pad172)") (class "Default")
      (node (ref "RPI-CM1") (pin "172") (pinfunction "HDMI0_TX2_N_172") (pintype "passive"))
    )
    (net (code "121") (name "unconnected-(RPI-CM1B-HDMI0_TX2_P-Pad170)") (class "Default")
      (node (ref "RPI-CM1") (pin "170") (pinfunction "HDMI0_TX2_P_170") (pintype "passive"))
    )
    (net (code "122") (name "unconnected-(RPI-CM1B-HDMI1_CEC-Pad149)") (class "Default")
      (node (ref "RPI-CM1") (pin "149") (pinfunction "HDMI1_CEC_149") (pintype "passive"))
    )
    (net (code "123") (name "unconnected-(RPI-CM1B-HDMI1_CLK_N-Pad166)") (class "Default")
      (node (ref "RPI-CM1") (pin "166") (pinfunction "HDMI1_CLK_N_166") (pintype "passive"))
    )
    (net (code "124") (name "unconnected-(RPI-CM1B-HDMI1_CLK_P-Pad164)") (class "Default")
      (node (ref "RPI-CM1") (pin "164") (pinfunction "HDMI1_CLK_P_164") (pintype "passive"))
    )
    (net (code "125") (name "unconnected-(RPI-CM1B-HDMI1_HOTPLUG-Pad143)") (class "Default")
      (node (ref "RPI-CM1") (pin "143") (pinfunction "HDMI1_HOTPLUG_143") (pintype "passive"))
    )
    (net (code "126") (name "unconnected-(RPI-CM1B-HDMI1_SCL-Pad147)") (class "Default")
      (node (ref "RPI-CM1") (pin "147") (pinfunction "HDMI1_SCL_147") (pintype "passive"))
    )
    (net (code "127") (name "unconnected-(RPI-CM1B-HDMI1_SDA-Pad145)") (class "Default")
      (node (ref "RPI-CM1") (pin "145") (pinfunction "HDMI1_SDA_145") (pintype "passive"))
    )
    (net (code "128") (name "unconnected-(RPI-CM1B-HDMI1_TX0_N-Pad160)") (class "Default")
      (node (ref "RPI-CM1") (pin "160") (pinfunction "HDMI1_TX0_N_160") (pintype "passive"))
    )
    (net (code "129") (name "unconnected-(RPI-CM1B-HDMI1_TX0_P-Pad158)") (class "Default")
      (node (ref "RPI-CM1") (pin "158") (pinfunction "HDMI1_TX0_P_158") (pintype "passive"))
    )
    (net (code "130") (name "unconnected-(RPI-CM1B-HDMI1_TX1_N-Pad154)") (class "Default")
      (node (ref "RPI-CM1") (pin "154") (pinfunction "HDMI1_TX1_N_154") (pintype "passive"))
    )
    (net (code "131") (name "unconnected-(RPI-CM1B-HDMI1_TX1_P-Pad152)") (class "Default")
      (node (ref "RPI-CM1") (pin "152") (pinfunction "HDMI1_TX1_P_152") (pintype "passive"))
    )
    (net (code "132") (name "unconnected-(RPI-CM1B-HDMI1_TX2_N-Pad148)") (class "Default")
      (node (ref "RPI-CM1") (pin "148") (pinfunction "HDMI1_TX2_N_148") (pintype "passive"))
    )
    (net (code "133") (name "unconnected-(RPI-CM1B-HDMI1_TX2_P-Pad146)") (class "Default")
      (node (ref "RPI-CM1") (pin "146") (pinfunction "HDMI1_TX2_P_146") (pintype "passive"))
    )
    (net (code "134") (name "unconnected-(RPI-CM1B-PCIE_CLK_N-Pad112)") (class "Default")
      (node (ref "RPI-CM1") (pin "112") (pinfunction "PCIE_CLK_N_112") (pintype "passive"))
    )
    (net (code "135") (name "unconnected-(RPI-CM1B-PCIE_CLK_P-Pad110)") (class "Default")
      (node (ref "RPI-CM1") (pin "110") (pinfunction "PCIE_CLK_P_110") (pintype "passive"))
    )
    (net (code "136") (name "unconnected-(RPI-CM1B-PCIE_CLK_~{REQ}-Pad102)") (class "Default")
      (node (ref "RPI-CM1") (pin "102") (pinfunction "PCIE_CLK_~{REQ}_102") (pintype "passive"))
    )
    (net (code "137") (name "unconnected-(RPI-CM1B-PCIE_RX_N-Pad118)") (class "Default")
      (node (ref "RPI-CM1") (pin "118") (pinfunction "PCIE_RX_N_118") (pintype "passive"))
    )
    (net (code "138") (name "unconnected-(RPI-CM1B-PCIE_RX_P-Pad116)") (class "Default")
      (node (ref "RPI-CM1") (pin "116") (pinfunction "PCIE_RX_P_116") (pintype "passive"))
    )
    (net (code "139") (name "unconnected-(RPI-CM1B-PCIE_TX_N-Pad124)") (class "Default")
      (node (ref "RPI-CM1") (pin "124") (pinfunction "PCIE_TX_N_124") (pintype "passive"))
    )
    (net (code "140") (name "unconnected-(RPI-CM1B-PCIE_TX_P-Pad122)") (class "Default")
      (node (ref "RPI-CM1") (pin "122") (pinfunction "PCIE_TX_P_122") (pintype "passive"))
    )
    (net (code "141") (name "unconnected-(RPI-CM1B-PCIE_~{RST}-Pad109)") (class "Default")
      (node (ref "RPI-CM1") (pin "109") (pinfunction "PCIE_~{RST}_109") (pintype "passive"))
    )
    (net (code "142") (name "unconnected-(RPI-CM1B-RESERVED-Pad104)") (class "Default")
      (node (ref "RPI-CM1") (pin "104") (pinfunction "RESERVED_104") (pintype "passive"))
    )
    (net (code "143") (name "unconnected-(RPI-CM1B-RESERVED-Pad106)") (class "Default")
      (node (ref "RPI-CM1") (pin "106") (pinfunction "RESERVED_106") (pintype "passive"))
    )
    (net (code "144") (name "unconnected-(RPI-CM1B-USB_N-Pad103)") (class "Default")
      (node (ref "RPI-CM1") (pin "103") (pinfunction "USB_N_103") (pintype "passive"))
    )
    (net (code "145") (name "unconnected-(RPI-CM1B-USB_OTG_ID-Pad101)") (class "Default")
      (node (ref "RPI-CM1") (pin "101") (pinfunction "USB_OTG_ID_101") (pintype "passive"))
    )
    (net (code "146") (name "unconnected-(RPI-CM1B-USB_P-Pad105)") (class "Default")
      (node (ref "RPI-CM1") (pin "105") (pinfunction "USB_P_105") (pintype "passive"))
    )
    (net (code "147") (name "unconnected-(RPI-CM1B-VDAC_COMP-Pad111)") (class "Default")
      (node (ref "RPI-CM1") (pin "111") (pinfunction "VDAC_COMP_111") (pintype "passive"))
    )
  )
)
